# MaxRam.net
KiCad netlist of a schematic drawn in EAGLE
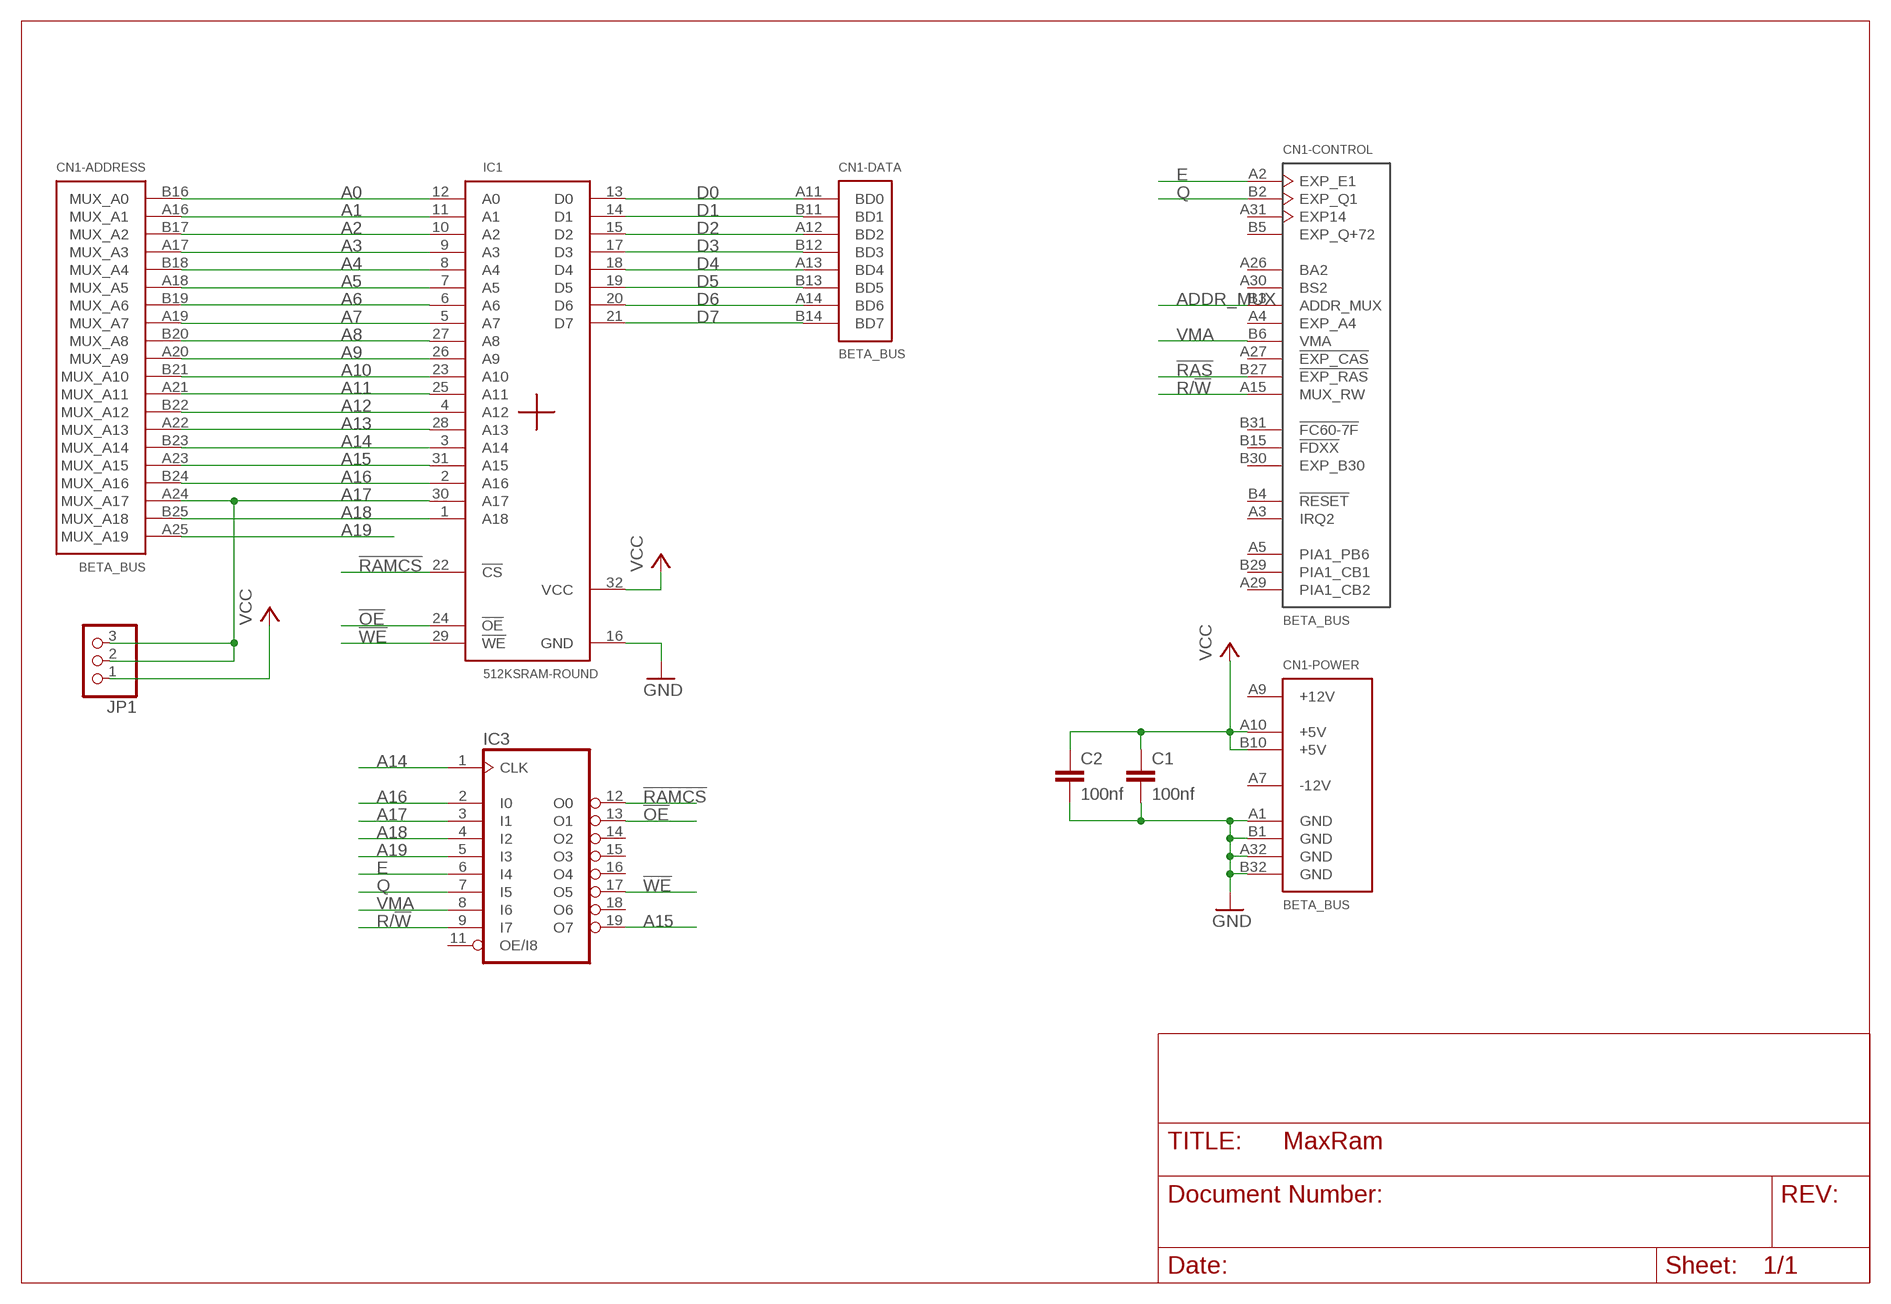
[diagram p0: schematic, sheet 1]

(export (version "E")
  (design (tool "Eeschema 10.0.6"))
  (components
    (comp (ref "C1")
      (value "100nf")
      (footprint "eagle-import:C025-025X050")
      (libsource (lib "eagle-import") (part "C-EU025-025X050"))
    )
    (comp (ref "C2")
      (value "100nf")
      (footprint "eagle-import:C025-025X050")
      (libsource (lib "eagle-import") (part "C-EU025-025X050"))
    )
    (comp (ref "CN1")
      (value "BETA_BUS")
      (footprint "eagle-import:MAB64")
      (libsource (lib "eagle-import") (part "BETA_BUS"))
    )
    (comp (ref "IC1")
      (value "512KSRAM-ROUND")
      (footprint "eagle-import:DIL32-ROUND")
      (libsource (lib "eagle-import") (part "512KSRAM-ROUND"))
    )
    (comp (ref "IC3")
      (value "16V8-ROUND")
      (footprint "eagle-import:DIL20-R")
      (libsource (lib "eagle-import") (part "16V8-ROUND"))
    )
    (comp (ref "JP1")
      (value "PINHD-1X3")
      (footprint "eagle-import:1X03")
      (libsource (lib "eagle-import") (part "PINHD-1X3"))
    )
  )
  (nets
    (net (code "1") (name "/+12V") (class "Default")
      (node (ref "CN1") (pin "A9") (pinfunction "+12V_A9") (pintype "power_in"))
    )
    (net (code "2") (name "/-12V") (class "Default")
      (node (ref "CN1") (pin "A7") (pinfunction "-12V_A7") (pintype "power_in"))
    )
    (net (code "3") (name "/A0") (class "Default")
      (node (ref "CN1") (pin "B16") (pinfunction "MUX_A0_B16") (pintype "output"))
      (node (ref "IC1") (pin "12") (pinfunction "A0_12") (pintype "input"))
    )
    (net (code "4") (name "/A1") (class "Default")
      (node (ref "CN1") (pin "A16") (pinfunction "MUX_A1_A16") (pintype "output"))
      (node (ref "IC1") (pin "11") (pinfunction "A1_11") (pintype "input"))
    )
    (net (code "5") (name "/A2") (class "Default")
      (node (ref "CN1") (pin "B17") (pinfunction "MUX_A2_B17") (pintype "output"))
      (node (ref "IC1") (pin "10") (pinfunction "A2_10") (pintype "input"))
    )
    (net (code "6") (name "/A3") (class "Default")
      (node (ref "CN1") (pin "A17") (pinfunction "MUX_A3_A17") (pintype "output"))
      (node (ref "IC1") (pin "9") (pinfunction "A3_9") (pintype "input"))
    )
    (net (code "7") (name "/A4") (class "Default")
      (node (ref "CN1") (pin "B18") (pinfunction "MUX_A4_B18") (pintype "output"))
      (node (ref "IC1") (pin "8") (pinfunction "A4_8") (pintype "input"))
    )
    (net (code "8") (name "/A5") (class "Default")
      (node (ref "CN1") (pin "A18") (pinfunction "MUX_A5_A18") (pintype "output"))
      (node (ref "IC1") (pin "7") (pinfunction "A5_7") (pintype "input"))
    )
    (net (code "9") (name "/A6") (class "Default")
      (node (ref "CN1") (pin "B19") (pinfunction "MUX_A6_B19") (pintype "output"))
      (node (ref "IC1") (pin "6") (pinfunction "A6_6") (pintype "input"))
    )
    (net (code "10") (name "/A7") (class "Default")
      (node (ref "CN1") (pin "A19") (pinfunction "MUX_A7_A19") (pintype "output"))
      (node (ref "IC1") (pin "5") (pinfunction "A7_5") (pintype "input"))
    )
    (net (code "11") (name "/A8") (class "Default")
      (node (ref "CN1") (pin "B20") (pinfunction "MUX_A8_B20") (pintype "output"))
      (node (ref "IC1") (pin "27") (pinfunction "A8_27") (pintype "input"))
    )
    (net (code "12") (name "/A9") (class "Default")
      (node (ref "CN1") (pin "A20") (pinfunction "MUX_A9_A20") (pintype "output"))
      (node (ref "IC1") (pin "26") (pinfunction "A9_26") (pintype "input"))
    )
    (net (code "13") (name "/A10") (class "Default")
      (node (ref "CN1") (pin "B21") (pinfunction "MUX_A10_B21") (pintype "output"))
      (node (ref "IC1") (pin "23") (pinfunction "A10_23") (pintype "input"))
    )
    (net (code "14") (name "/A11") (class "Default")
      (node (ref "CN1") (pin "A21") (pinfunction "MUX_A11_A21") (pintype "output"))
      (node (ref "IC1") (pin "25") (pinfunction "A11_25") (pintype "input"))
    )
    (net (code "15") (name "/A12") (class "Default")
      (node (ref "CN1") (pin "B22") (pinfunction "MUX_A12_B22") (pintype "output"))
      (node (ref "IC1") (pin "4") (pinfunction "A12_4") (pintype "input"))
    )
    (net (code "16") (name "/A13") (class "Default")
      (node (ref "CN1") (pin "A22") (pinfunction "MUX_A13_A22") (pintype "output"))
      (node (ref "IC1") (pin "28") (pinfunction "A13_28") (pintype "input"))
    )
    (net (code "17") (name "/A14") (class "Default")
      (node (ref "CN1") (pin "B23") (pinfunction "MUX_A14_B23") (pintype "output"))
      (node (ref "IC1") (pin "3") (pinfunction "A14_3") (pintype "input"))
      (node (ref "IC3") (pin "1") (pinfunction "CLK_1") (pintype "input"))
    )
    (net (code "18") (name "/A15") (class "Default")
      (node (ref "CN1") (pin "A23") (pinfunction "MUX_A15_A23") (pintype "output"))
      (node (ref "IC1") (pin "31") (pinfunction "A15_31") (pintype "input"))
      (node (ref "IC3") (pin "19") (pinfunction "O7_19") (pintype "bidirectional"))
    )
    (net (code "19") (name "/A16") (class "Default")
      (node (ref "CN1") (pin "B24") (pinfunction "MUX_A16_B24") (pintype "output"))
      (node (ref "IC1") (pin "2") (pinfunction "A16_2") (pintype "input"))
      (node (ref "IC3") (pin "2") (pinfunction "I0_2") (pintype "input"))
    )
    (net (code "20") (name "/A17") (class "Default")
      (node (ref "CN1") (pin "A24") (pinfunction "MUX_A17_A24") (pintype "output"))
      (node (ref "IC1") (pin "30") (pinfunction "A17_30") (pintype "input"))
      (node (ref "IC3") (pin "3") (pinfunction "I1_3") (pintype "input"))
      (node (ref "JP1") (pin "2") (pinfunction "2_2") (pintype "passive"))
      (node (ref "JP1") (pin "3") (pinfunction "3_3") (pintype "passive"))
    )
    (net (code "21") (name "/A18") (class "Default")
      (node (ref "CN1") (pin "B25") (pinfunction "MUX_A18_B25") (pintype "output"))
      (node (ref "IC1") (pin "1") (pinfunction "A18_1") (pintype "input"))
      (node (ref "IC3") (pin "4") (pinfunction "I2_4") (pintype "input"))
    )
    (net (code "22") (name "/A19") (class "Default")
      (node (ref "CN1") (pin "A25") (pinfunction "MUX_A19_A25") (pintype "output"))
      (node (ref "IC3") (pin "5") (pinfunction "I3_5") (pintype "input"))
    )
    (net (code "23") (name "/ADDR_MUX") (class "Default")
      (node (ref "CN1") (pin "B3") (pinfunction "ADDR_MUX_B3") (pintype "output"))
    )
    (net (code "24") (name "/D0") (class "Default")
      (node (ref "CN1") (pin "A11") (pinfunction "BD0_A11") (pintype "bidirectional"))
      (node (ref "IC1") (pin "13") (pinfunction "D0_13") (pintype "bidirectional"))
    )
    (net (code "25") (name "/D1") (class "Default")
      (node (ref "CN1") (pin "B11") (pinfunction "BD1_B11") (pintype "bidirectional"))
      (node (ref "IC1") (pin "14") (pinfunction "D1_14") (pintype "bidirectional"))
    )
    (net (code "26") (name "/D2") (class "Default")
      (node (ref "CN1") (pin "A12") (pinfunction "BD2_A12") (pintype "bidirectional"))
      (node (ref "IC1") (pin "15") (pinfunction "D2_15") (pintype "bidirectional"))
    )
    (net (code "27") (name "/D3") (class "Default")
      (node (ref "CN1") (pin "B12") (pinfunction "BD3_B12") (pintype "bidirectional"))
      (node (ref "IC1") (pin "17") (pinfunction "D3_17") (pintype "bidirectional"))
    )
    (net (code "28") (name "/D4") (class "Default")
      (node (ref "CN1") (pin "A13") (pinfunction "BD4_A13") (pintype "bidirectional"))
      (node (ref "IC1") (pin "18") (pinfunction "D4_18") (pintype "bidirectional"))
    )
    (net (code "29") (name "/D5") (class "Default")
      (node (ref "CN1") (pin "B13") (pinfunction "BD5_B13") (pintype "bidirectional"))
      (node (ref "IC1") (pin "19") (pinfunction "D5_19") (pintype "bidirectional"))
    )
    (net (code "30") (name "/D6") (class "Default")
      (node (ref "CN1") (pin "A14") (pinfunction "BD6_A14") (pintype "bidirectional"))
      (node (ref "IC1") (pin "20") (pinfunction "D6_20") (pintype "bidirectional"))
    )
    (net (code "31") (name "/D7") (class "Default")
      (node (ref "CN1") (pin "B14") (pinfunction "BD7_B14") (pintype "bidirectional"))
      (node (ref "IC1") (pin "21") (pinfunction "D7_21") (pintype "bidirectional"))
    )
    (net (code "32") (name "/E") (class "Default")
      (node (ref "CN1") (pin "A2") (pinfunction "EXP_E1_A2") (pintype "output"))
      (node (ref "IC3") (pin "6") (pinfunction "I4_6") (pintype "input"))
    )
    (net (code "33") (name "/Q") (class "Default")
      (node (ref "CN1") (pin "B2") (pinfunction "EXP_Q1_B2") (pintype "output"))
      (node (ref "IC3") (pin "7") (pinfunction "I5_7") (pintype "input"))
    )
    (net (code "34") (name "/R{slash}~{W}") (class "Default")
      (node (ref "CN1") (pin "A15") (pinfunction "MUX_RW_A15") (pintype "output"))
      (node (ref "IC3") (pin "9") (pinfunction "I7_9") (pintype "input"))
    )
    (net (code "35") (name "/VMA") (class "Default")
      (node (ref "CN1") (pin "B6") (pinfunction "VMA_B6") (pintype "output"))
      (node (ref "IC3") (pin "8") (pinfunction "I6_8") (pintype "input"))
    )
    (net (code "36") (name "/~{OE}") (class "Default")
      (node (ref "IC1") (pin "24") (pinfunction "~{OE}_24") (pintype "input"))
      (node (ref "IC3") (pin "13") (pinfunction "O1_13") (pintype "bidirectional"))
    )
    (net (code "37") (name "/~{RAMCS}") (class "Default")
      (node (ref "IC1") (pin "22") (pinfunction "~{CS}_22") (pintype "input"))
      (node (ref "IC3") (pin "12") (pinfunction "O0_12") (pintype "bidirectional"))
    )
    (net (code "38") (name "/~{RAS}") (class "Default")
      (node (ref "CN1") (pin "B27") (pinfunction "~{EXP_RAS}_B27") (pintype "output"))
    )
    (net (code "39") (name "/~{WE}") (class "Default")
      (node (ref "IC1") (pin "29") (pinfunction "~{WE}_29") (pintype "input"))
      (node (ref "IC3") (pin "17") (pinfunction "O5_17") (pintype "bidirectional"))
    )
    (net (code "40") (name "GND") (class "Default")
      (node (ref "C1") (pin "2") (pinfunction "2_2") (pintype "passive"))
      (node (ref "C2") (pin "2") (pinfunction "2_2") (pintype "passive"))
      (node (ref "CN1") (pin "A1") (pinfunction "GND_A1") (pintype "power_in"))
      (node (ref "CN1") (pin "A32") (pinfunction "GND_A32") (pintype "power_in"))
      (node (ref "CN1") (pin "B1") (pinfunction "GND_B1") (pintype "power_in"))
      (node (ref "CN1") (pin "B32") (pinfunction "GND_B32") (pintype "power_in"))
      (node (ref "IC1") (pin "16") (pinfunction "GND_16") (pintype "power_in"))
    )
    (net (code "41") (name "VCC") (class "Default")
      (node (ref "C1") (pin "1") (pinfunction "1_1") (pintype "passive"))
      (node (ref "C2") (pin "1") (pinfunction "1_1") (pintype "passive"))
      (node (ref "CN1") (pin "A10") (pinfunction "+5V_A10") (pintype "power_in"))
      (node (ref "CN1") (pin "B10") (pinfunction "+5V_B10") (pintype "power_in"))
      (node (ref "IC1") (pin "32") (pinfunction "VCC_32") (pintype "power_in"))
      (node (ref "JP1") (pin "1") (pinfunction "1_1") (pintype "passive"))
    )
    (net (code "42") (name "unconnected-(CN1B-BA2-PadA26)") (class "Default")
      (node (ref "CN1") (pin "A26") (pinfunction "BA2_A26") (pintype "output"))
    )
    (net (code "43") (name "unconnected-(CN1B-BS2-PadA30)") (class "Default")
      (node (ref "CN1") (pin "A30") (pinfunction "BS2_A30") (pintype "passive"))
    )
    (net (code "44") (name "unconnected-(CN1B-EXP14-PadA31)") (class "Default")
      (node (ref "CN1") (pin "A31") (pinfunction "EXP14_A31") (pintype "output"))
    )
    (net (code "45") (name "unconnected-(CN1B-EXP_A4-PadA4)") (class "Default")
      (node (ref "CN1") (pin "A4") (pinfunction "EXP_A4_A4") (pintype "output"))
    )
    (net (code "46") (name "unconnected-(CN1B-EXP_B30-PadB30)") (class "Default")
      (node (ref "CN1") (pin "B30") (pinfunction "EXP_B30_B30") (pintype "output"))
    )
    (net (code "47") (name "unconnected-(CN1B-EXP_Q+72-PadB5)") (class "Default")
      (node (ref "CN1") (pin "B5") (pinfunction "EXP_Q+72_B5") (pintype "output"))
    )
    (net (code "48") (name "unconnected-(CN1B-IRQ2-PadA3)") (class "Default")
      (node (ref "CN1") (pin "A3") (pinfunction "IRQ2_A3") (pintype "bidirectional"))
    )
    (net (code "49") (name "unconnected-(CN1B-PIA1_CB1-PadB29)") (class "Default")
      (node (ref "CN1") (pin "B29") (pinfunction "PIA1_CB1_B29") (pintype "bidirectional"))
    )
    (net (code "50") (name "unconnected-(CN1B-PIA1_CB2-PadA29)") (class "Default")
      (node (ref "CN1") (pin "A29") (pinfunction "PIA1_CB2_A29") (pintype "bidirectional"))
    )
    (net (code "51") (name "unconnected-(CN1B-PIA1_PB6-PadA5)") (class "Default")
      (node (ref "CN1") (pin "A5") (pinfunction "PIA1_PB6_A5") (pintype "bidirectional"))
    )
    (net (code "52") (name "unconnected-(CN1B-~{EXP_CAS}-PadA27)") (class "Default")
      (node (ref "CN1") (pin "A27") (pinfunction "~{EXP_CAS}_A27") (pintype "output"))
    )
    (net (code "53") (name "unconnected-(CN1B-~{FC60-7F}-PadB31)") (class "Default")
      (node (ref "CN1") (pin "B31") (pinfunction "~{FC60-7F}_B31") (pintype "output"))
    )
    (net (code "54") (name "unconnected-(CN1B-~{FDXX}-PadB15)") (class "Default")
      (node (ref "CN1") (pin "B15") (pinfunction "~{FDXX}_B15") (pintype "output"))
    )
    (net (code "55") (name "unconnected-(CN1B-~{RESET}-PadB4)") (class "Default")
      (node (ref "CN1") (pin "B4") (pinfunction "~{RESET}_B4") (pintype "bidirectional"))
    )
    (net (code "56") (name "unconnected-(IC3A-O2-Pad14)") (class "Default")
      (node (ref "IC3") (pin "14") (pinfunction "O2_14") (pintype "bidirectional"))
    )
    (net (code "57") (name "unconnected-(IC3A-O3-Pad15)") (class "Default")
      (node (ref "IC3") (pin "15") (pinfunction "O3_15") (pintype "bidirectional"))
    )
    (net (code "58") (name "unconnected-(IC3A-O4-Pad16)") (class "Default")
      (node (ref "IC3") (pin "16") (pinfunction "O4_16") (pintype "bidirectional"))
    )
    (net (code "59") (name "unconnected-(IC3A-O6-Pad18)") (class "Default")
      (node (ref "IC3") (pin "18") (pinfunction "O6_18") (pintype "bidirectional"))
    )
    (net (code "60") (name "unconnected-(IC3A-OE{slash}I8-Pad11)") (class "Default")
      (node (ref "IC3") (pin "11") (pinfunction "OE/I8_11") (pintype "input"))
    )
  )
)
